# V0_41_programmer.net
KiCad netlist of a schematic drawn in EAGLE
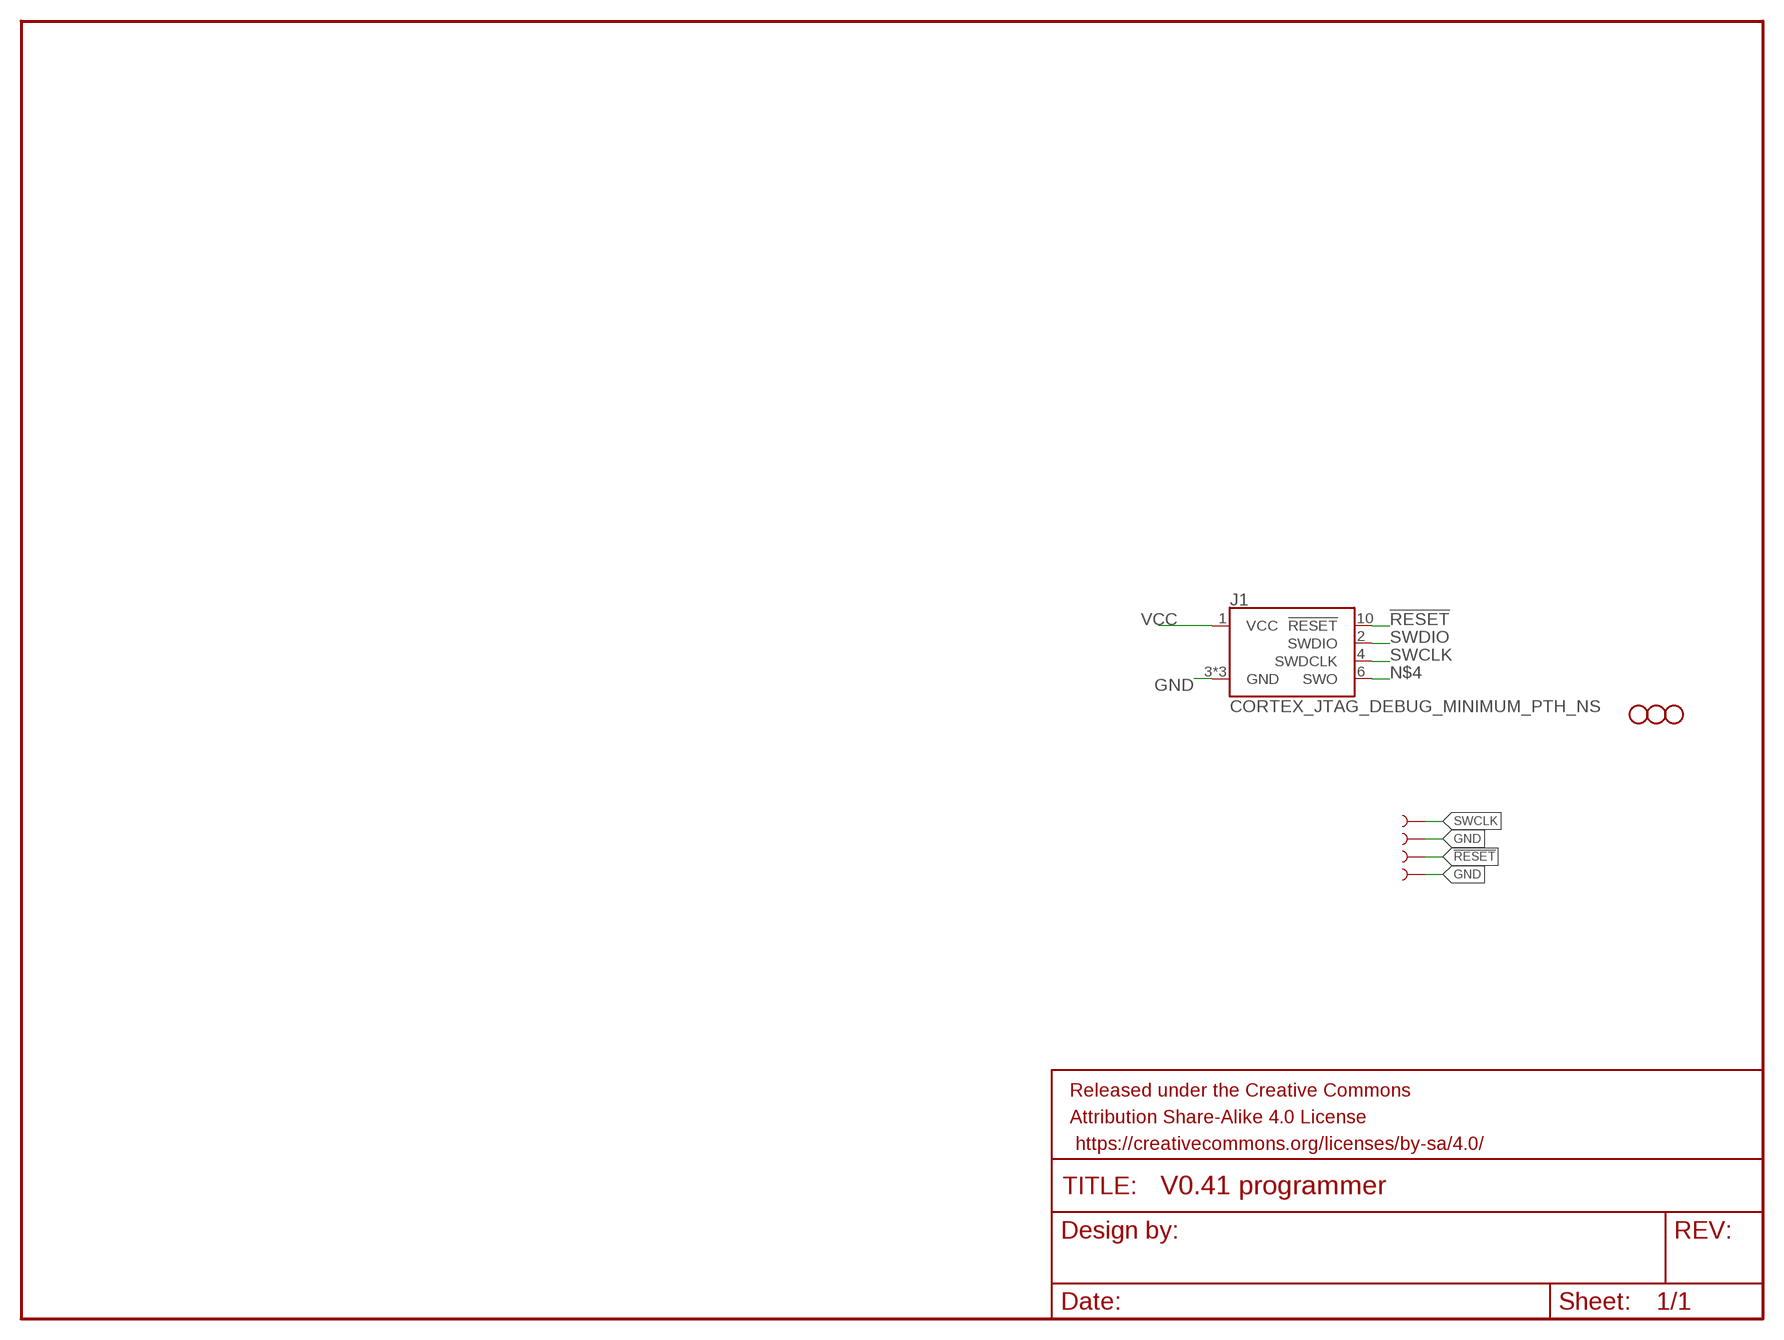
[diagram p0: schematic, sheet 1]

(export (version "E")
  (design (tool "Eeschema 10.0.6"))
  (components
    (comp (ref "FRAME1")
      (value "FRAME-LETTERNO_PACKAGE")
      (footprint "eagle-import:DUMMY")
      (fields (field (name "DESIGNER") "Nobody"))
      (libsource (lib "eagle-import") (part "FRAME-LETTERNO_PACKAGE"))
    )
    (comp (ref "H1")
      (value "STAND-OFFTIGHT")
      (footprint "eagle-import:STAND-OFF-TIGHT")
      (libsource (lib "eagle-import") (part "STAND-OFFTIGHT"))
    )
    (comp (ref "H2")
      (value "STAND-OFFTIGHT")
      (footprint "eagle-import:STAND-OFF-TIGHT")
      (libsource (lib "eagle-import") (part "STAND-OFFTIGHT"))
    )
    (comp (ref "H3")
      (value "STAND-OFFTIGHT")
      (footprint "eagle-import:STAND-OFF-TIGHT")
      (libsource (lib "eagle-import") (part "STAND-OFFTIGHT"))
    )
    (comp (ref "J1")
      (value "CORTEX_JTAG_DEBUG_MINIMUM_PTH_NS")
      (footprint "eagle-import:2X5-PTH-1.27MM-NO_SILK")
      (libsource (lib "eagle-import") (part "CORTEX_JTAG_DEBUG_MINIMUM_PTH_NS"))
    )
    (comp (ref "TP1")
      (value "TEST-POINT3")
      (footprint "eagle-import:PAD.03X.03")
      (libsource (lib "eagle-import") (part "TEST-POINT3"))
    )
    (comp (ref "TP2")
      (value "TEST-POINT3")
      (footprint "eagle-import:PAD.03X.03")
      (libsource (lib "eagle-import") (part "TEST-POINT3"))
    )
    (comp (ref "TP3")
      (value "TEST-POINT3")
      (footprint "eagle-import:PAD.03X.03")
      (libsource (lib "eagle-import") (part "TEST-POINT3"))
    )
    (comp (ref "TP4")
      (value "TEST-POINT3")
      (footprint "eagle-import:PAD.03X.03")
      (libsource (lib "eagle-import") (part "TEST-POINT3"))
    )
  )
  (nets
    (net (code "1") (name "/N$4") (class "Default")
      (node (ref "J1") (pin "6") (pinfunction "SWO_6") (pintype "bidirectional"))
    )
    (net (code "2") (name "/SWDIO") (class "Default")
      (node (ref "J1") (pin "2") (pinfunction "SWDIO_2") (pintype "bidirectional"))
    )
    (net (code "3") (name "/VCC") (class "Default")
      (node (ref "J1") (pin "1") (pinfunction "VCC_1") (pintype "bidirectional"))
    )
    (net (code "4") (name "/~{RESET}") (class "Default")
      (node (ref "J1") (pin "10") (pinfunction "~{RESET}_10") (pintype "bidirectional"))
      (node (ref "TP3") (pin "P$1") (pinfunction "1_P$1") (pintype "bidirectional"))
    )
    (net (code "5") (name "GND") (class "Default")
      (node (ref "J1") (pin "3") (pinfunction "GND_3") (pintype "bidirectional"))
      (node (ref "J1") (pin "5") (pinfunction "GND_5") (pintype "bidirectional"))
      (node (ref "J1") (pin "9") (pinfunction "GND_9") (pintype "bidirectional"))
      (node (ref "TP2") (pin "P$1") (pinfunction "1_P$1") (pintype "bidirectional"))
      (node (ref "TP4") (pin "P$1") (pinfunction "1_P$1") (pintype "bidirectional"))
    )
    (net (code "6") (name "SWCLK") (class "Default")
      (node (ref "J1") (pin "4") (pinfunction "SWDCLK_4") (pintype "bidirectional"))
      (node (ref "TP1") (pin "P$1") (pinfunction "1_P$1") (pintype "bidirectional"))
    )
  )
)
